# Arduino_Board.net
KiCad netlist of a schematic drawn in EAGLE
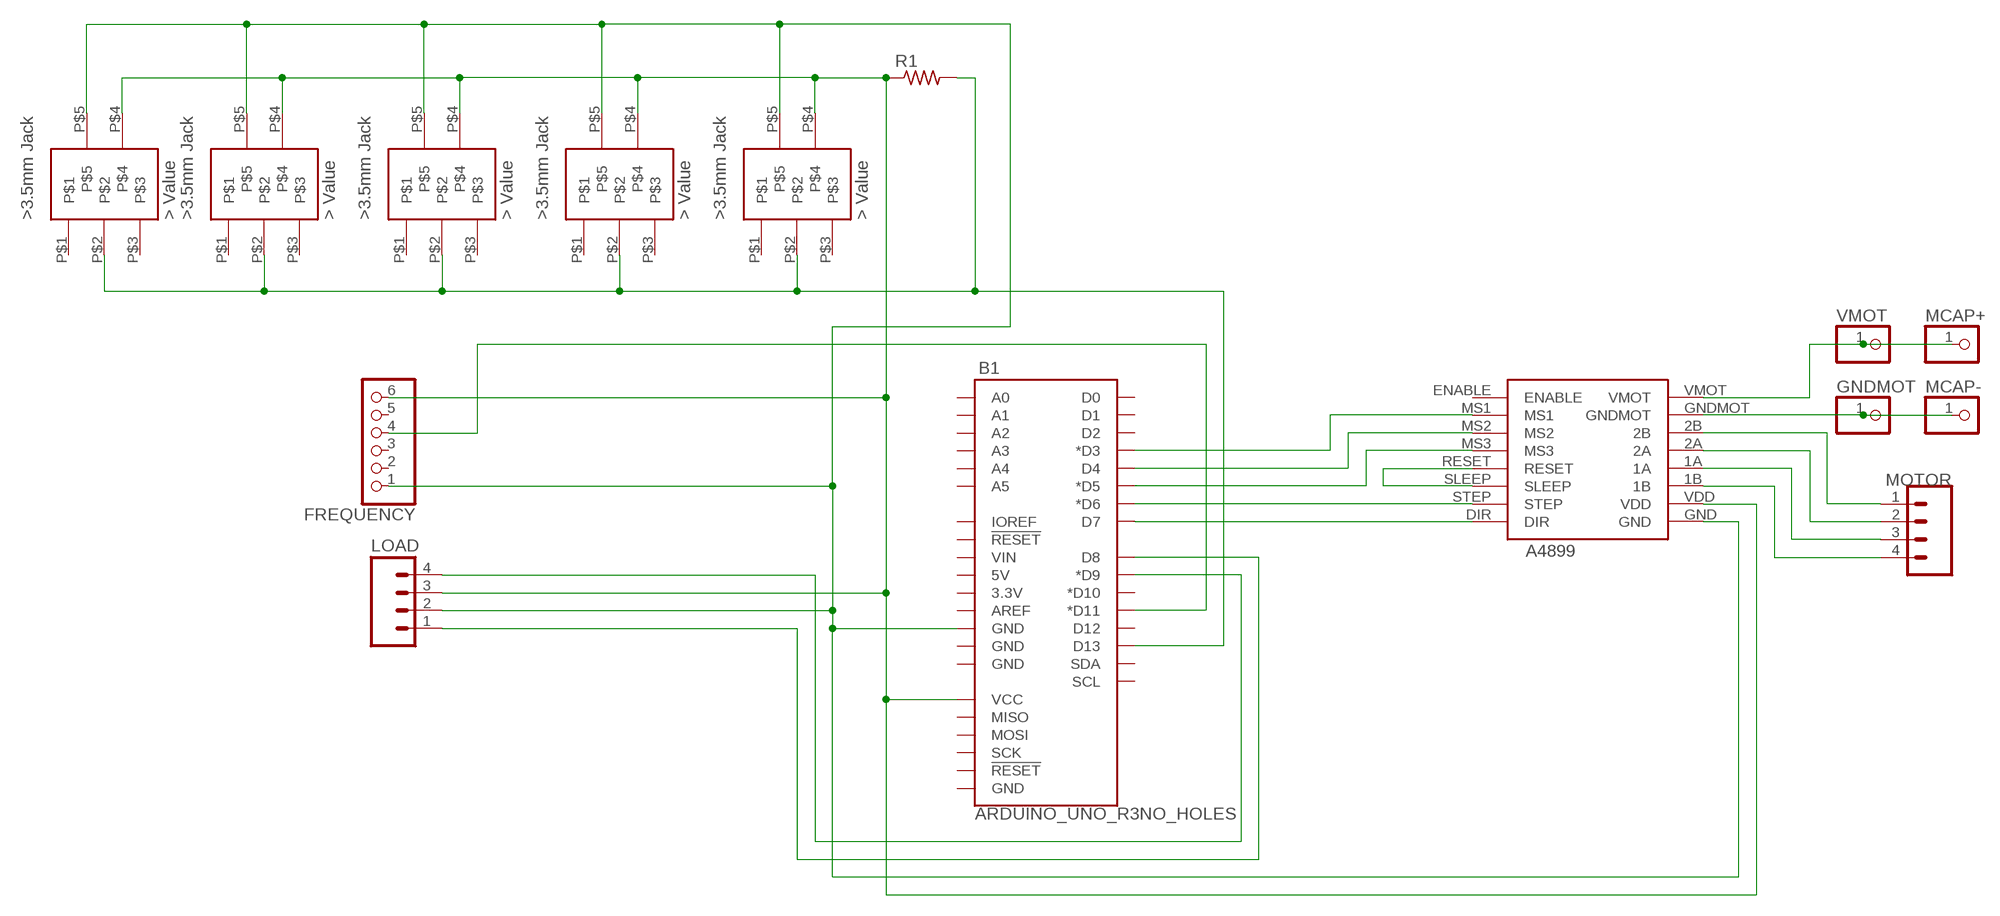
[diagram p0: schematic, sheet 1]

(export (version "E")
  (design (tool "Eeschema 10.0.6"))
  (components
    (comp (ref "3.5MM_JACK1")
      (value "3.5MM_JACK")
      (footprint "eagle-import:3.5MM_JACK")
      (libsource (lib "eagle-import") (part "3.5MM_JACK"))
    )
    (comp (ref "3.5MM_JACK2")
      (value "3.5MM_JACK")
      (footprint "eagle-import:3.5MM_JACK")
      (libsource (lib "eagle-import") (part "3.5MM_JACK"))
    )
    (comp (ref "3.5MM_JACK3")
      (value "3.5MM_JACK")
      (footprint "eagle-import:3.5MM_JACK")
      (libsource (lib "eagle-import") (part "3.5MM_JACK"))
    )
    (comp (ref "3.5MM_JACK4")
      (value "3.5MM_JACK")
      (footprint "eagle-import:3.5MM_JACK")
      (libsource (lib "eagle-import") (part "3.5MM_JACK"))
    )
    (comp (ref "3.5MM_JACK5")
      (value "3.5MM_JACK")
      (footprint "eagle-import:3.5MM_JACK")
      (libsource (lib "eagle-import") (part "3.5MM_JACK"))
    )
    (comp (ref "A4899_1")
      (value "A4899")
      (footprint "eagle-import:A4899")
      (libsource (lib "eagle-import") (part "A4899"))
    )
    (comp (ref "B1")
      (value "ARDUINO_UNO_R3NO_HOLES")
      (footprint "eagle-import:ARDUINO_R3_NO_HOLES")
      (libsource (lib "eagle-import") (part "ARDUINO_UNO_R3NO_HOLES"))
    )
    (comp (ref "FREQUENCY")
      (value "PINHD-1X6")
      (footprint "eagle-import:1X06")
      (libsource (lib "eagle-import") (part "PINHD-1X6"))
    )
    (comp (ref "GNDMOT")
      (value "PINHD-1X1")
      (footprint "eagle-import:1X01")
      (libsource (lib "eagle-import") (part "PINHD-1X1"))
    )
    (comp (ref "LOAD")
      (value "M04PTH")
      (footprint "eagle-import:1X04")
      (libsource (lib "eagle-import") (part "M04PTH"))
    )
    (comp (ref "MCAP+")
      (value "PINHD-1X1")
      (footprint "eagle-import:1X01")
      (libsource (lib "eagle-import") (part "PINHD-1X1"))
    )
    (comp (ref "MCAP-")
      (value "PINHD-1X1")
      (footprint "eagle-import:1X01")
      (libsource (lib "eagle-import") (part "PINHD-1X1"))
    )
    (comp (ref "MOTOR")
      (value "M04PTH")
      (footprint "eagle-import:1X04")
      (libsource (lib "eagle-import") (part "M04PTH"))
    )
    (comp (ref "R1")
      (value "R-US_0204/5")
      (footprint "eagle-import:0204_5")
      (libsource (lib "eagle-import") (part "R-US_0204/5"))
    )
    (comp (ref "VMOT")
      (value "PINHD-1X1")
      (footprint "eagle-import:1X01")
      (libsource (lib "eagle-import") (part "PINHD-1X1"))
    )
  )
  (nets
    (net (code "1") (name "Net-(3.5MM_JACK1-PadP$2)") (class "Default")
      (node (ref "3.5MM_JACK1") (pin "P$2") (pinfunction "P$2_P$2") (pintype "bidirectional"))
      (node (ref "3.5MM_JACK2") (pin "P$2") (pinfunction "P$2_P$2") (pintype "bidirectional"))
      (node (ref "3.5MM_JACK3") (pin "P$2") (pinfunction "P$2_P$2") (pintype "bidirectional"))
      (node (ref "3.5MM_JACK4") (pin "P$2") (pinfunction "P$2_P$2") (pintype "bidirectional"))
      (node (ref "3.5MM_JACK5") (pin "P$2") (pinfunction "P$2_P$2") (pintype "bidirectional"))
      (node (ref "B1") (pin "D13") (pinfunction "D13_D13") (pintype "bidirectional"))
      (node (ref "R1") (pin "2") (pinfunction "2_2") (pintype "passive"))
    )
    (net (code "2") (name "Net-(3.5MM_JACK1-PadP$4)") (class "Default")
      (node (ref "3.5MM_JACK1") (pin "P$4") (pinfunction "P$4_P$4") (pintype "bidirectional"))
      (node (ref "3.5MM_JACK2") (pin "P$4") (pinfunction "P$4_P$4") (pintype "bidirectional"))
      (node (ref "3.5MM_JACK3") (pin "P$4") (pinfunction "P$4_P$4") (pintype "bidirectional"))
      (node (ref "3.5MM_JACK4") (pin "P$4") (pinfunction "P$4_P$4") (pintype "bidirectional"))
      (node (ref "3.5MM_JACK5") (pin "P$4") (pinfunction "P$4_P$4") (pintype "bidirectional"))
      (node (ref "A4899_1") (pin "VDD") (pinfunction "VDD_VDD") (pintype "bidirectional"))
      (node (ref "B1") (pin "VCC") (pinfunction "VCC_VCC") (pintype "bidirectional"))
      (node (ref "FREQUENCY") (pin "6") (pinfunction "6_6") (pintype "passive"))
      (node (ref "LOAD") (pin "3") (pinfunction "3_3") (pintype "passive"))
      (node (ref "R1") (pin "1") (pinfunction "1_1") (pintype "passive"))
    )
    (net (code "3") (name "Net-(3.5MM_JACK1-PadP$5)") (class "Default")
      (node (ref "3.5MM_JACK1") (pin "P$5") (pinfunction "P$5_P$5") (pintype "bidirectional"))
      (node (ref "3.5MM_JACK2") (pin "P$5") (pinfunction "P$5_P$5") (pintype "bidirectional"))
      (node (ref "3.5MM_JACK3") (pin "P$5") (pinfunction "P$5_P$5") (pintype "bidirectional"))
      (node (ref "3.5MM_JACK4") (pin "P$5") (pinfunction "P$5_P$5") (pintype "bidirectional"))
      (node (ref "3.5MM_JACK5") (pin "P$5") (pinfunction "P$5_P$5") (pintype "bidirectional"))
      (node (ref "A4899_1") (pin "GND") (pinfunction "GND_GND") (pintype "bidirectional"))
      (node (ref "B1") (pin "GND@4") (pinfunction "GND_GND@4") (pintype "bidirectional"))
      (node (ref "FREQUENCY") (pin "1") (pinfunction "1_1") (pintype "passive"))
      (node (ref "LOAD") (pin "2") (pinfunction "2_2") (pintype "passive"))
    )
    (net (code "4") (name "Net-(A4899_1-Pad1A)") (class "Default")
      (node (ref "A4899_1") (pin "1A") (pinfunction "1A_1A") (pintype "bidirectional"))
      (node (ref "MOTOR") (pin "3") (pinfunction "3_3") (pintype "passive"))
    )
    (net (code "5") (name "Net-(A4899_1-Pad1B)") (class "Default")
      (node (ref "A4899_1") (pin "1B") (pinfunction "1B_1B") (pintype "bidirectional"))
      (node (ref "MOTOR") (pin "4") (pinfunction "4_4") (pintype "passive"))
    )
    (net (code "6") (name "Net-(A4899_1-Pad2A)") (class "Default")
      (node (ref "A4899_1") (pin "2A") (pinfunction "2A_2A") (pintype "bidirectional"))
      (node (ref "MOTOR") (pin "2") (pinfunction "2_2") (pintype "passive"))
    )
    (net (code "7") (name "Net-(A4899_1-Pad2B)") (class "Default")
      (node (ref "A4899_1") (pin "2B") (pinfunction "2B_2B") (pintype "bidirectional"))
      (node (ref "MOTOR") (pin "1") (pinfunction "1_1") (pintype "passive"))
    )
    (net (code "8") (name "Net-(A4899_1-PadDIR)") (class "Default")
      (node (ref "A4899_1") (pin "DIR") (pinfunction "DIR_DIR") (pintype "bidirectional"))
      (node (ref "B1") (pin "D7") (pinfunction "D7_D7") (pintype "bidirectional"))
    )
    (net (code "9") (name "Net-(A4899_1-PadGNDMOT)") (class "Default")
      (node (ref "A4899_1") (pin "GNDMOT") (pinfunction "GNDMOT_GNDMOT") (pintype "bidirectional"))
      (node (ref "GNDMOT") (pin "1") (pinfunction "1_1") (pintype "passive"))
      (node (ref "MCAP-") (pin "1") (pinfunction "1_1") (pintype "passive"))
    )
    (net (code "10") (name "Net-(A4899_1-PadMS2)") (class "Default")
      (node (ref "A4899_1") (pin "MS2") (pinfunction "MS2_MS2") (pintype "bidirectional"))
      (node (ref "B1") (pin "D4") (pinfunction "D4_D4") (pintype "bidirectional"))
    )
    (net (code "11") (name "Net-(A4899_1-PadRESET)") (class "Default")
      (node (ref "A4899_1") (pin "RESET") (pinfunction "RESET_RESET") (pintype "bidirectional"))
      (node (ref "A4899_1") (pin "SLEEP") (pinfunction "SLEEP_SLEEP") (pintype "bidirectional"))
    )
    (net (code "12") (name "Net-(A4899_1-PadVMOT)") (class "Default")
      (node (ref "A4899_1") (pin "VMOT") (pinfunction "VMOT_VMOT") (pintype "bidirectional"))
      (node (ref "MCAP+") (pin "1") (pinfunction "1_1") (pintype "passive"))
      (node (ref "VMOT") (pin "1") (pinfunction "1_1") (pintype "passive"))
    )
    (net (code "13") (name "Net-(B1-*D3)") (class "Default")
      (node (ref "A4899_1") (pin "MS1") (pinfunction "MS1_MS1") (pintype "bidirectional"))
      (node (ref "B1") (pin "D3") (pinfunction "*D3_D3") (pintype "bidirectional"))
    )
    (net (code "14") (name "Net-(B1-*D5)") (class "Default")
      (node (ref "A4899_1") (pin "MS3") (pinfunction "MS3_MS3") (pintype "bidirectional"))
      (node (ref "B1") (pin "D5") (pinfunction "*D5_D5") (pintype "bidirectional"))
    )
    (net (code "15") (name "Net-(B1-*D6)") (class "Default")
      (node (ref "A4899_1") (pin "STEP") (pinfunction "STEP_STEP") (pintype "bidirectional"))
      (node (ref "B1") (pin "D6") (pinfunction "*D6_D6") (pintype "bidirectional"))
    )
    (net (code "16") (name "Net-(B1-*D9)") (class "Default")
      (node (ref "B1") (pin "D9") (pinfunction "*D9_D9") (pintype "bidirectional"))
      (node (ref "LOAD") (pin "4") (pinfunction "4_4") (pintype "passive"))
    )
    (net (code "17") (name "Net-(B1-*D11)") (class "Default")
      (node (ref "B1") (pin "D11") (pinfunction "*D11_D11") (pintype "bidirectional"))
      (node (ref "FREQUENCY") (pin "4") (pinfunction "4_4") (pintype "passive"))
    )
    (net (code "18") (name "Net-(B1-PadD8)") (class "Default")
      (node (ref "B1") (pin "D8") (pinfunction "D8_D8") (pintype "bidirectional"))
      (node (ref "LOAD") (pin "1") (pinfunction "1_1") (pintype "passive"))
    )
    (net (code "19") (name "unconnected-(3.5MM_JACK1-PadP$1)") (class "Default")
      (node (ref "3.5MM_JACK1") (pin "P$1") (pinfunction "P$1_P$1") (pintype "bidirectional"))
    )
    (net (code "20") (name "unconnected-(3.5MM_JACK1-PadP$3)") (class "Default")
      (node (ref "3.5MM_JACK1") (pin "P$3") (pinfunction "P$3_P$3") (pintype "bidirectional"))
    )
    (net (code "21") (name "unconnected-(3.5MM_JACK2-PadP$1)") (class "Default")
      (node (ref "3.5MM_JACK2") (pin "P$1") (pinfunction "P$1_P$1") (pintype "bidirectional"))
    )
    (net (code "22") (name "unconnected-(3.5MM_JACK2-PadP$3)") (class "Default")
      (node (ref "3.5MM_JACK2") (pin "P$3") (pinfunction "P$3_P$3") (pintype "bidirectional"))
    )
    (net (code "23") (name "unconnected-(3.5MM_JACK3-PadP$1)") (class "Default")
      (node (ref "3.5MM_JACK3") (pin "P$1") (pinfunction "P$1_P$1") (pintype "bidirectional"))
    )
    (net (code "24") (name "unconnected-(3.5MM_JACK3-PadP$3)") (class "Default")
      (node (ref "3.5MM_JACK3") (pin "P$3") (pinfunction "P$3_P$3") (pintype "bidirectional"))
    )
    (net (code "25") (name "unconnected-(3.5MM_JACK4-PadP$1)") (class "Default")
      (node (ref "3.5MM_JACK4") (pin "P$1") (pinfunction "P$1_P$1") (pintype "bidirectional"))
    )
    (net (code "26") (name "unconnected-(3.5MM_JACK4-PadP$3)") (class "Default")
      (node (ref "3.5MM_JACK4") (pin "P$3") (pinfunction "P$3_P$3") (pintype "bidirectional"))
    )
    (net (code "27") (name "unconnected-(3.5MM_JACK5-PadP$1)") (class "Default")
      (node (ref "3.5MM_JACK5") (pin "P$1") (pinfunction "P$1_P$1") (pintype "bidirectional"))
    )
    (net (code "28") (name "unconnected-(3.5MM_JACK5-PadP$3)") (class "Default")
      (node (ref "3.5MM_JACK5") (pin "P$3") (pinfunction "P$3_P$3") (pintype "bidirectional"))
    )
    (net (code "29") (name "unconnected-(A4899_1-PadENABLE)") (class "Default")
      (node (ref "A4899_1") (pin "ENABLE") (pinfunction "ENABLE_ENABLE") (pintype "bidirectional"))
    )
    (net (code "30") (name "unconnected-(B1-*D10-PadD10)") (class "Default")
      (node (ref "B1") (pin "D10") (pinfunction "*D10_D10") (pintype "bidirectional"))
    )
    (net (code "31") (name "unconnected-(B1-GND-PadGND@1)") (class "Default")
      (node (ref "B1") (pin "GND@1") (pinfunction "GND_GND@1") (pintype "bidirectional"))
    )
    (net (code "32") (name "unconnected-(B1-GND-PadGND@2)") (class "Default")
      (node (ref "B1") (pin "GND@2") (pinfunction "GND_GND@2") (pintype "bidirectional"))
    )
    (net (code "33") (name "unconnected-(B1-GND-PadGND@3)") (class "Default")
      (node (ref "B1") (pin "GND@3") (pinfunction "GND_GND@3") (pintype "bidirectional"))
    )
    (net (code "34") (name "unconnected-(B1-Pad3.3V)") (class "Default")
      (node (ref "B1") (pin "3.3V") (pinfunction "3.3V_3.3V") (pintype "bidirectional"))
    )
    (net (code "35") (name "unconnected-(B1-Pad5V)") (class "Default")
      (node (ref "B1") (pin "5V") (pinfunction "5V_5V") (pintype "bidirectional"))
    )
    (net (code "36") (name "unconnected-(B1-PadA0)") (class "Default")
      (node (ref "B1") (pin "A0") (pinfunction "A0_A0") (pintype "bidirectional"))
    )
    (net (code "37") (name "unconnected-(B1-PadA1)") (class "Default")
      (node (ref "B1") (pin "A1") (pinfunction "A1_A1") (pintype "bidirectional"))
    )
    (net (code "38") (name "unconnected-(B1-PadA2)") (class "Default")
      (node (ref "B1") (pin "A2") (pinfunction "A2_A2") (pintype "bidirectional"))
    )
    (net (code "39") (name "unconnected-(B1-PadA3)") (class "Default")
      (node (ref "B1") (pin "A3") (pinfunction "A3_A3") (pintype "bidirectional"))
    )
    (net (code "40") (name "unconnected-(B1-PadA4)") (class "Default")
      (node (ref "B1") (pin "A4") (pinfunction "A4_A4") (pintype "bidirectional"))
    )
    (net (code "41") (name "unconnected-(B1-PadA5)") (class "Default")
      (node (ref "B1") (pin "A5") (pinfunction "A5_A5") (pintype "bidirectional"))
    )
    (net (code "42") (name "unconnected-(B1-PadAREF)") (class "Default")
      (node (ref "B1") (pin "AREF") (pinfunction "AREF_AREF") (pintype "bidirectional"))
    )
    (net (code "43") (name "unconnected-(B1-PadD0)") (class "Default")
      (node (ref "B1") (pin "D0") (pinfunction "D0_D0") (pintype "bidirectional"))
    )
    (net (code "44") (name "unconnected-(B1-PadD1)") (class "Default")
      (node (ref "B1") (pin "D1") (pinfunction "D1_D1") (pintype "bidirectional"))
    )
    (net (code "45") (name "unconnected-(B1-PadD2)") (class "Default")
      (node (ref "B1") (pin "D2") (pinfunction "D2_D2") (pintype "bidirectional"))
    )
    (net (code "46") (name "unconnected-(B1-PadD12)") (class "Default")
      (node (ref "B1") (pin "D12") (pinfunction "D12_D12") (pintype "bidirectional"))
    )
    (net (code "47") (name "unconnected-(B1-PadIOREF)") (class "Default")
      (node (ref "B1") (pin "IOREF") (pinfunction "IOREF_IOREF") (pintype "bidirectional"))
    )
    (net (code "48") (name "unconnected-(B1-PadMISO)") (class "Default")
      (node (ref "B1") (pin "MISO") (pinfunction "MISO_MISO") (pintype "bidirectional"))
    )
    (net (code "49") (name "unconnected-(B1-PadMOSI)") (class "Default")
      (node (ref "B1") (pin "MOSI") (pinfunction "MOSI_MOSI") (pintype "bidirectional"))
    )
    (net (code "50") (name "unconnected-(B1-PadSCK)") (class "Default")
      (node (ref "B1") (pin "SCK") (pinfunction "SCK_SCK") (pintype "bidirectional"))
    )
    (net (code "51") (name "unconnected-(B1-PadSCL)") (class "Default")
      (node (ref "B1") (pin "SCL") (pinfunction "SCL_SCL") (pintype "bidirectional"))
    )
    (net (code "52") (name "unconnected-(B1-PadSDA)") (class "Default")
      (node (ref "B1") (pin "SDA") (pinfunction "SDA_SDA") (pintype "bidirectional"))
    )
    (net (code "53") (name "unconnected-(B1-PadVIN)") (class "Default")
      (node (ref "B1") (pin "VIN") (pinfunction "VIN_VIN") (pintype "bidirectional"))
    )
    (net (code "54") (name "unconnected-(B1-~{RESET}-PadRESET@1)") (class "Default")
      (node (ref "B1") (pin "RESET@1") (pinfunction "~{RESET}_RESET@1") (pintype "bidirectional"))
    )
    (net (code "55") (name "unconnected-(B1-~{RESET}-PadRESET@2)") (class "Default")
      (node (ref "B1") (pin "RESET@2") (pinfunction "~{RESET}_RESET@2") (pintype "bidirectional"))
    )
    (net (code "56") (name "unconnected-(FREQUENCY-Pad2)") (class "Default")
      (node (ref "FREQUENCY") (pin "2") (pinfunction "2_2") (pintype "passive"))
    )
    (net (code "57") (name "unconnected-(FREQUENCY-Pad3)") (class "Default")
      (node (ref "FREQUENCY") (pin "3") (pinfunction "3_3") (pintype "passive"))
    )
    (net (code "58") (name "unconnected-(FREQUENCY-Pad5)") (class "Default")
      (node (ref "FREQUENCY") (pin "5") (pinfunction "5_5") (pintype "passive"))
    )
  )
)
